# Wemos-ESP8266_MAX7219_v5.net
KiCad netlist of a schematic drawn in EAGLE
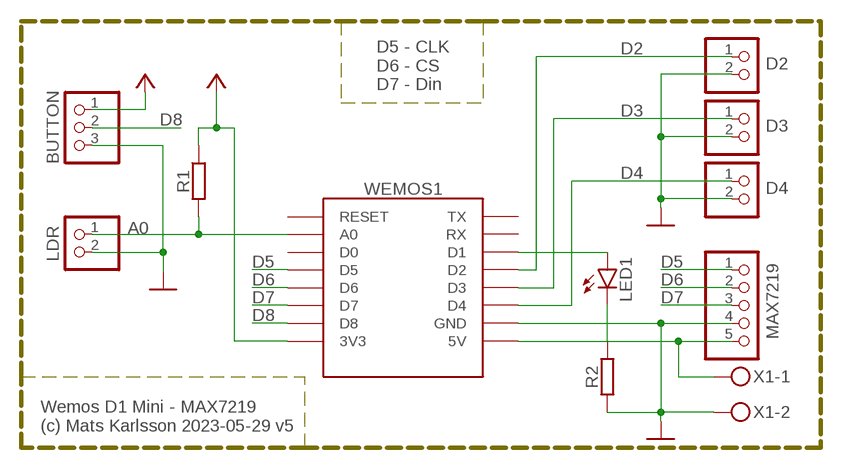
[diagram p0: schematic, sheet 1]

(export (version "E")
  (design (tool "Eeschema 10.0.6"))
  (components
    (comp (ref "BUTTON")
      (value "PINHD-1X3")
      (footprint "eagle-import:1X03")
      (libsource (lib "eagle-import") (part "PINHD-1X3"))
    )
    (comp (ref "D2")
      (value "PINHD-1X2")
      (footprint "eagle-import:1X02")
      (libsource (lib "eagle-import") (part "PINHD-1X2"))
    )
    (comp (ref "D3")
      (value "PINHD-1X2")
      (footprint "eagle-import:1X02")
      (libsource (lib "eagle-import") (part "PINHD-1X2"))
    )
    (comp (ref "D4")
      (value "PINHD-1X2")
      (footprint "eagle-import:1X02")
      (libsource (lib "eagle-import") (part "PINHD-1X2"))
    )
    (comp (ref "LDR")
      (value "PINHD-1X2")
      (footprint "eagle-import:1X02")
      (libsource (lib "eagle-import") (part "PINHD-1X2"))
    )
    (comp (ref "LED1")
      (value "LEDCHIPLED_1206")
      (footprint "eagle-import:CHIPLED_1206")
      (libsource (lib "eagle-import") (part "LEDCHIPLED_1206"))
    )
    (comp (ref "MAX7219")
      (value "PINHD-1X5")
      (footprint "eagle-import:1X05")
      (libsource (lib "eagle-import") (part "PINHD-1X5"))
    )
    (comp (ref "R1")
      (value "R-EU_M0805")
      (footprint "eagle-import:M0805")
      (libsource (lib "eagle-import") (part "R-EU_M0805"))
    )
    (comp (ref "R2")
      (value "R-EU_M0805")
      (footprint "eagle-import:M0805")
      (libsource (lib "eagle-import") (part "R-EU_M0805"))
    )
    (comp (ref "WEMOS1")
      (value "WEMOS-D1-MINI")
      (footprint "eagle-import:WEMOS-D1-MINI")
      (libsource (lib "eagle-import") (part "WEMOS-D1-MINI"))
    )
    (comp (ref "X1")
      (value "W237-102")
      (footprint "eagle-import:W237-102")
      (fields (field (name "MPN") "237-102"))
      (libsource (lib "eagle-import") (part "W237-102"))
    )
  )
  (nets
    (net (code "1") (name "/A0") (class "Default")
      (node (ref "LDR") (pin "1") (pinfunction "1_1") (pintype "passive"))
      (node (ref "R1") (pin "2") (pinfunction "2_2") (pintype "passive"))
      (node (ref "WEMOS1") (pin "A0") (pinfunction "A0_A0") (pintype "bidirectional"))
    )
    (net (code "2") (name "/D2") (class "Default")
      (node (ref "D2") (pin "1") (pinfunction "1_1") (pintype "passive"))
      (node (ref "WEMOS1") (pin "D2") (pinfunction "D2_D2") (pintype "bidirectional"))
    )
    (net (code "3") (name "/D3") (class "Default")
      (node (ref "D3") (pin "1") (pinfunction "1_1") (pintype "passive"))
      (node (ref "WEMOS1") (pin "D3") (pinfunction "D3_D3") (pintype "bidirectional"))
    )
    (net (code "4") (name "/D4") (class "Default")
      (node (ref "D4") (pin "1") (pinfunction "1_1") (pintype "passive"))
      (node (ref "WEMOS1") (pin "D4") (pinfunction "D4_D4") (pintype "bidirectional"))
    )
    (net (code "5") (name "/D5") (class "Default")
      (node (ref "MAX7219") (pin "1") (pinfunction "1_1") (pintype "passive"))
      (node (ref "WEMOS1") (pin "D5") (pinfunction "D5_D5") (pintype "bidirectional"))
    )
    (net (code "6") (name "/D6") (class "Default")
      (node (ref "MAX7219") (pin "2") (pinfunction "2_2") (pintype "passive"))
      (node (ref "WEMOS1") (pin "D6") (pinfunction "D6_D6") (pintype "bidirectional"))
    )
    (net (code "7") (name "/D7") (class "Default")
      (node (ref "MAX7219") (pin "3") (pinfunction "3_3") (pintype "passive"))
      (node (ref "WEMOS1") (pin "D7") (pinfunction "D7_D7") (pintype "bidirectional"))
    )
    (net (code "8") (name "/D8") (class "Default")
      (node (ref "BUTTON") (pin "2") (pinfunction "2_2") (pintype "passive"))
      (node (ref "WEMOS1") (pin "D8") (pinfunction "D8_D8") (pintype "bidirectional"))
    )
    (net (code "9") (name "GND") (class "Default")
      (node (ref "BUTTON") (pin "3") (pinfunction "3_3") (pintype "passive"))
      (node (ref "D2") (pin "2") (pinfunction "2_2") (pintype "passive"))
      (node (ref "D3") (pin "2") (pinfunction "2_2") (pintype "passive"))
      (node (ref "D4") (pin "2") (pinfunction "2_2") (pintype "passive"))
      (node (ref "LDR") (pin "2") (pinfunction "2_2") (pintype "passive"))
      (node (ref "MAX7219") (pin "4") (pinfunction "4_4") (pintype "passive"))
      (node (ref "R2") (pin "2") (pinfunction "2_2") (pintype "passive"))
      (node (ref "WEMOS1") (pin "GND") (pinfunction "GND_GND") (pintype "bidirectional"))
      (node (ref "X1") (pin "2") (pinfunction "KL_2") (pintype "passive"))
    )
    (net (code "10") (name "Net-(LED1-PadA)") (class "Default")
      (node (ref "LED1") (pin "A") (pinfunction "A_A") (pintype "passive"))
      (node (ref "WEMOS1") (pin "D1") (pinfunction "D1_D1") (pintype "bidirectional"))
    )
    (net (code "11") (name "Net-(LED1-PadC)") (class "Default")
      (node (ref "LED1") (pin "C") (pinfunction "C_C") (pintype "passive"))
      (node (ref "R2") (pin "1") (pinfunction "1_1") (pintype "passive"))
    )
    (net (code "12") (name "Net-(X1A-KL)") (class "Default")
      (node (ref "MAX7219") (pin "5") (pinfunction "5_5") (pintype "passive"))
      (node (ref "WEMOS1") (pin "5V") (pinfunction "5V_5V") (pintype "bidirectional"))
      (node (ref "X1") (pin "1") (pinfunction "KL_1") (pintype "passive"))
    )
    (net (code "13") (name "VCC") (class "Default")
      (node (ref "BUTTON") (pin "1") (pinfunction "1_1") (pintype "passive"))
      (node (ref "R1") (pin "1") (pinfunction "1_1") (pintype "passive"))
      (node (ref "WEMOS1") (pin "3V3") (pinfunction "3V3_3V3") (pintype "bidirectional"))
    )
    (net (code "14") (name "unconnected-(WEMOS1-PadD0)") (class "Default")
      (node (ref "WEMOS1") (pin "D0") (pinfunction "D0_D0") (pintype "bidirectional"))
    )
    (net (code "15") (name "unconnected-(WEMOS1-PadRESET)") (class "Default")
      (node (ref "WEMOS1") (pin "RESET") (pinfunction "RESET_RESET") (pintype "bidirectional"))
    )
    (net (code "16") (name "unconnected-(WEMOS1-PadRX)") (class "Default")
      (node (ref "WEMOS1") (pin "RX") (pinfunction "RX_RX") (pintype "bidirectional"))
    )
    (net (code "17") (name "unconnected-(WEMOS1-PadTX)") (class "Default")
      (node (ref "WEMOS1") (pin "TX") (pinfunction "TX_TX") (pintype "bidirectional"))
    )
  )
)
